# Schematic01.net
KiCad netlist of a schematic drawn in Altium Designer
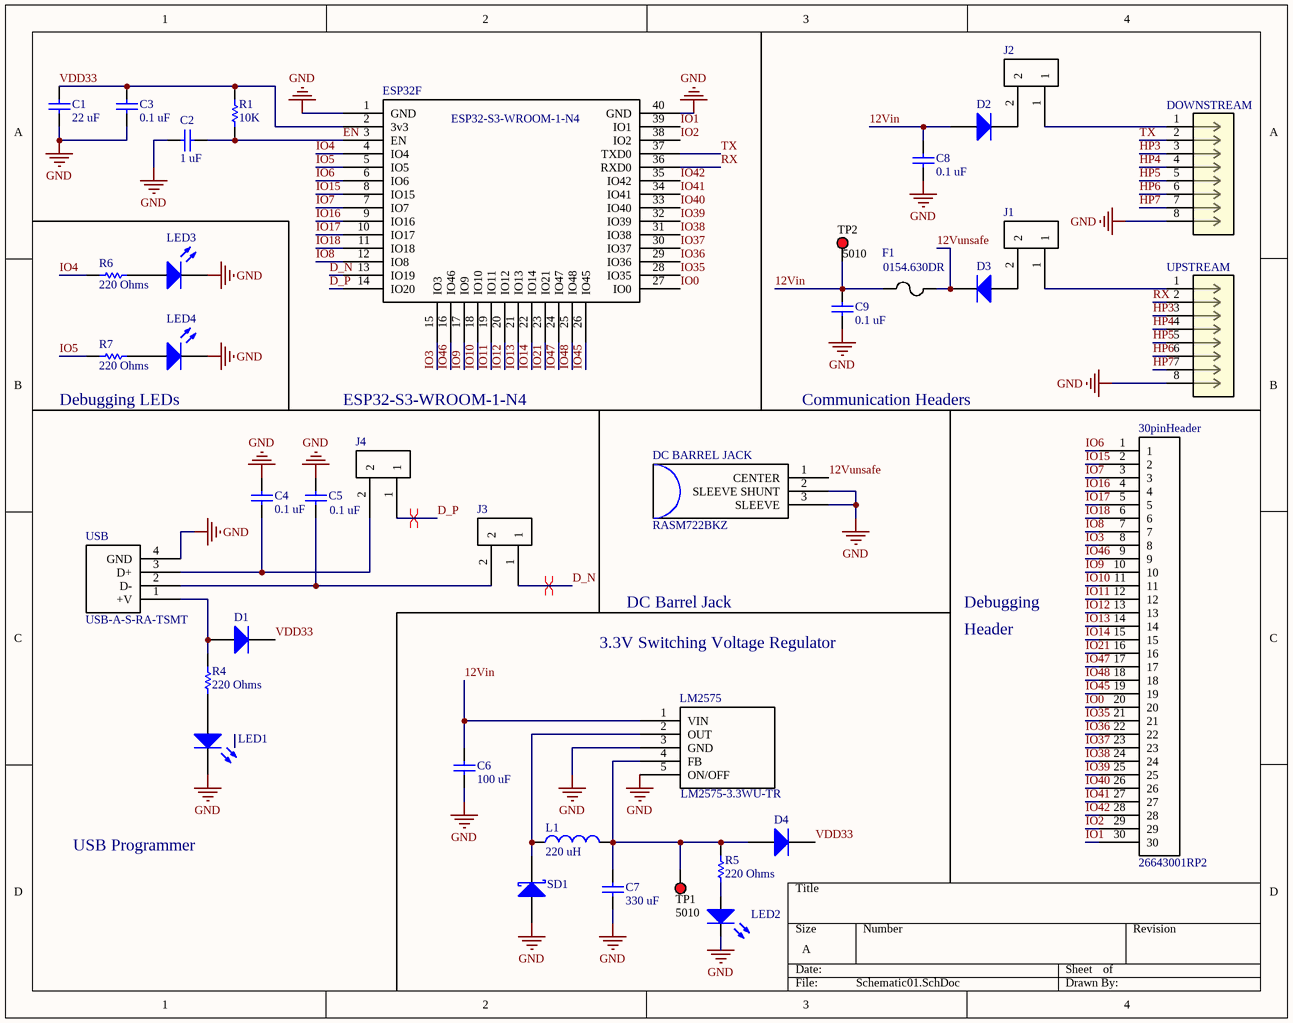
[diagram p0: Schematic01.SchDoc]

(export (version "E")
  (design (tool "Eeschema 10.0.6"))
  (components
    (comp (ref "30pinHeader")
      (value "26643001RP2")
      (description "Board Connector")
      (libsource (lib "egreetis") (part "26643001RP2-Symbol-1"))
    )
    (comp (ref "C1")
      (value "22 uF")
      (description "Capacitor")
      (libsource (lib "Simulation Generic Components") (part "Capacitor"))
    )
    (comp (ref "C2")
      (value "1 uF")
      (description "Capacitor")
      (libsource (lib "Simulation Generic Components") (part "Capacitor"))
    )
    (comp (ref "C3")
      (value "0.1 uF")
      (description "Capacitor")
      (libsource (lib "Simulation Generic Components") (part "Capacitor"))
    )
    (comp (ref "C4")
      (value "0.1 uF")
      (description "Capacitor")
      (libsource (lib "Simulation Generic Components") (part "Capacitor"))
    )
    (comp (ref "C5")
      (value "0.1 uF")
      (description "Capacitor")
      (libsource (lib "Simulation Generic Components") (part "Capacitor"))
    )
    (comp (ref "C6")
      (value "100 uF")
      (description "Capacitor")
      (libsource (lib "Simulation Generic Components") (part "Capacitor"))
    )
    (comp (ref "C7")
      (value "330 uF")
      (description "Capacitor")
      (libsource (lib "Simulation Generic Components") (part "Capacitor"))
    )
    (comp (ref "C8")
      (value "0.1 uF")
      (description "Capacitor")
      (libsource (lib "Simulation Generic Components") (part "Capacitor"))
    )
    (comp (ref "C9")
      (value "0.1 uF")
      (description "Capacitor")
      (libsource (lib "Simulation Generic Components") (part "Capacitor"))
    )
    (comp (ref "D1") (value "Diode") (libsource (lib "Simulation Generic Components") (part "Diode")))
    (comp (ref "D2") (value "Diode") (libsource (lib "Simulation Generic Components") (part "Diode")))
    (comp (ref "D3") (value "Diode") (libsource (lib "Simulation Generic Components") (part "Diode")))
    (comp (ref "D4") (value "Diode") (libsource (lib "Simulation Generic Components") (part "Diode")))
    (comp (ref "DC BARREL JACK")
      (value "RASM722BKZ")
      (description "Connector, DC Power Jack, BKZ Locking Series, 2.0mm Surface Mount")
      (libsource (lib "egreetis") (part "RASM722BKZ-Symbol-1"))
    )
    (comp (ref "DOWNSTREAM")
      (value "702460801")
      (footprint "CONN_7024608xx_MOL")
      (description "No Description Available")
      (libsource (lib "egreetis") (part "702460801"))
    )
    (comp (ref "ESP32F")
      (value "ESP32-S3-WROOM-1-N4")
      (description "WiFi-Modul 802.11/BT 2, 4-2, 5GHz 150Mb/s")
      (libsource (lib "egreetis") (part "ESP32-S3-WROOM-1-N4-Symbol-1"))
    )
    (comp (ref "F1")
      (value "0154.630DR")
      (footprint "0154Series_LTF")
      (description "No Description Available")
      (libsource (lib "0154P630DR") (part "0154.630DR"))
    )
    (comp (ref "J1")
      (value "26640201RP2")
      (description "Board Connector")
      (libsource (lib "egreetis") (part "26640201RP2-Symbol-1"))
    )
    (comp (ref "J2")
      (value "26640201RP2")
      (description "Board Connector")
      (libsource (lib "egreetis") (part "26640201RP2-Symbol-1"))
    )
    (comp (ref "J3")
      (value "26640201RP2")
      (description "Board Connector")
      (libsource (lib "egreetis") (part "26640201RP2-Symbol-1"))
    )
    (comp (ref "J4")
      (value "26640201RP2")
      (description "Board Connector")
      (libsource (lib "egreetis") (part "26640201RP2-Symbol-1"))
    )
    (comp (ref "L1")
      (value "220 uH")
      (description "Inductor")
      (libsource (lib "Simulation Generic Components") (part "Inductor"))
    )
    (comp (ref "LED1")
      (value "Light-Emitting Diode")
      (libsource (lib "Simulation Generic Components") (part "LED"))
    )
    (comp (ref "LED2")
      (value "Light-Emitting Diode")
      (libsource (lib "Simulation Generic Components") (part "LED"))
    )
    (comp (ref "LED3")
      (value "Light-Emitting Diode")
      (libsource (lib "Simulation Generic Components") (part "LED"))
    )
    (comp (ref "LED4")
      (value "Light-Emitting Diode")
      (libsource (lib "Simulation Generic Components") (part "LED"))
    )
    (comp (ref "LM2575")
      (value "LM2575-3.3WUTR")
      (description "LM2575 Series 3.3 V 1 A 52 KHz High-Efficiency Step-Down Buck Regulator-TO-263-5")
      (libsource (lib "egreetis") (part "LM2575-3.3WU-TR"))
    )
    (comp (ref "R1")
      (value "10K")
      (description "Resistor")
      (libsource (lib "Simulation Generic Components") (part "Resistor"))
    )
    (comp (ref "R4")
      (value "220 Ohms")
      (description "Resistor")
      (libsource (lib "Simulation Generic Components") (part "Resistor"))
    )
    (comp (ref "R5")
      (value "220 Ohms")
      (description "Resistor")
      (libsource (lib "Simulation Generic Components") (part "Resistor"))
    )
    (comp (ref "R6")
      (value "220 Ohms")
      (description "Resistor")
      (libsource (lib "Simulation Generic Components") (part "Resistor"))
    )
    (comp (ref "R7")
      (value "220 Ohms")
      (description "Resistor")
      (libsource (lib "Simulation Generic Components") (part "Resistor"))
    )
    (comp (ref "SD1")
      (value "Schottky Diode")
      (libsource (lib "Simulation Generic Components") (part "Schottky Diode"))
    )
    (comp (ref "TP1")
      (value "5010")
      (footprint "KSTN-5010_V")
      (description "Interconnection Device")
      (libsource (lib "egreetis") (part "TESTPOINT_RED"))
    )
    (comp (ref "TP2")
      (value "5010")
      (footprint "KSTN-5010_V")
      (description "Interconnection Device")
      (libsource (lib "egreetis") (part "TESTPOINT_RED"))
    )
    (comp (ref "UPSTREAM")
      (value "702460801")
      (footprint "CONN_7024608xx_MOL")
      (description "No Description Available")
      (libsource (lib "egreetis") (part "702460801"))
    )
    (comp (ref "USB")
      (value "USB-A-S-RA-TSMT")
      (description "Conn USB 2.0 Type A F 4 POS Solder RA SMD 4 Terminal 1 Port")
      (libsource (lib "egreetis") (part "USB-A-S-RA-TSMT-Symbol-1"))
    )
  )
  (nets
    (net (code "1") (name "/12Vin") (class "Default")
      (node (ref "C6") (pin "2") (pinfunction "2_2") (pintype "passive"))
      (node (ref "C8") (pin "2") (pinfunction "2_2") (pintype "passive"))
      (node (ref "C9") (pin "2") (pinfunction "2_2") (pintype "passive"))
      (node (ref "D2") (pin "1") (pinfunction "A_1") (pintype "passive"))
      (node (ref "F1") (pin "1") (pinfunction "1_1") (pintype "passive"))
      (node (ref "LM2575") (pin "1") (pinfunction "VIN_1") (pintype "passive"))
      (node (ref "TP2") (pin "1") (pinfunction "1_1") (pintype "passive"))
    )
    (net (code "2") (name "/12Vunsafe") (class "Default")
      (node (ref "D3") (pin "2") (pinfunction "K_2") (pintype "passive"))
      (node (ref "DC BARREL JACK") (pin "1") (pinfunction "CENTER_1") (pintype "passive"))
      (node (ref "F1") (pin "2") (pinfunction "2_2") (pintype "passive"))
    )
    (net (code "3") (name "/D_N") (class "Default")
      (node (ref "ESP32F") (pin "13") (pinfunction "IO19_13") (pintype "passive"))
      (node (ref "J3") (pin "1") (pinfunction "1_1") (pintype "passive"))
    )
    (net (code "4") (name "/D_P") (class "Default")
      (node (ref "ESP32F") (pin "14") (pinfunction "IO20_14") (pintype "passive"))
      (node (ref "J4") (pin "1") (pinfunction "1_1") (pintype "passive"))
    )
    (net (code "5") (name "/EN") (class "Default")
      (node (ref "C2") (pin "2") (pinfunction "2_2") (pintype "passive"))
      (node (ref "ESP32F") (pin "3") (pinfunction "EN_3") (pintype "passive"))
      (node (ref "R1") (pin "1") (pinfunction "1_1") (pintype "passive"))
    )
    (net (code "6") (name "/HP3") (class "Default")
      (node (ref "DOWNSTREAM") (pin "3") (pinfunction "3_3") (pintype "passive"))
      (node (ref "UPSTREAM") (pin "3") (pinfunction "3_3") (pintype "passive"))
    )
    (net (code "7") (name "/HP4") (class "Default")
      (node (ref "DOWNSTREAM") (pin "4") (pinfunction "4_4") (pintype "passive"))
      (node (ref "UPSTREAM") (pin "4") (pinfunction "4_4") (pintype "passive"))
    )
    (net (code "8") (name "/HP5") (class "Default")
      (node (ref "DOWNSTREAM") (pin "5") (pinfunction "5_5") (pintype "passive"))
      (node (ref "UPSTREAM") (pin "5") (pinfunction "5_5") (pintype "passive"))
    )
    (net (code "9") (name "/HP6") (class "Default")
      (node (ref "DOWNSTREAM") (pin "6") (pinfunction "6_6") (pintype "passive"))
      (node (ref "UPSTREAM") (pin "6") (pinfunction "6_6") (pintype "passive"))
    )
    (net (code "10") (name "/HP7") (class "Default")
      (node (ref "DOWNSTREAM") (pin "7") (pinfunction "7_7") (pintype "passive"))
      (node (ref "UPSTREAM") (pin "7") (pinfunction "7_7") (pintype "passive"))
    )
    (net (code "11") (name "/IO0") (class "Default")
      (node (ref "30pinHeader") (pin "20") (pinfunction "20_20") (pintype "passive"))
      (node (ref "ESP32F") (pin "27") (pinfunction "IO0_27") (pintype "passive"))
    )
    (net (code "12") (name "/IO1") (class "Default")
      (node (ref "30pinHeader") (pin "30") (pinfunction "30_30") (pintype "passive"))
      (node (ref "ESP32F") (pin "39") (pinfunction "IO1_39") (pintype "passive"))
    )
    (net (code "13") (name "/IO2") (class "Default")
      (node (ref "30pinHeader") (pin "29") (pinfunction "29_29") (pintype "passive"))
      (node (ref "ESP32F") (pin "38") (pinfunction "IO2_38") (pintype "passive"))
    )
    (net (code "14") (name "/IO3") (class "Default")
      (node (ref "30pinHeader") (pin "8") (pinfunction "8_8") (pintype "passive"))
      (node (ref "ESP32F") (pin "15") (pinfunction "IO3_15") (pintype "passive"))
    )
    (net (code "15") (name "/IO4") (class "Default")
      (node (ref "ESP32F") (pin "4") (pinfunction "IO4_4") (pintype "passive"))
      (node (ref "R6") (pin "1") (pinfunction "1_1") (pintype "passive"))
    )
    (net (code "16") (name "/IO5") (class "Default")
      (node (ref "ESP32F") (pin "5") (pinfunction "IO5_5") (pintype "passive"))
      (node (ref "R7") (pin "1") (pinfunction "1_1") (pintype "passive"))
    )
    (net (code "17") (name "/IO6") (class "Default")
      (node (ref "30pinHeader") (pin "1") (pinfunction "1_1") (pintype "passive"))
      (node (ref "ESP32F") (pin "6") (pinfunction "IO6_6") (pintype "passive"))
    )
    (net (code "18") (name "/IO7") (class "Default")
      (node (ref "30pinHeader") (pin "3") (pinfunction "3_3") (pintype "passive"))
      (node (ref "ESP32F") (pin "7") (pinfunction "IO7_7") (pintype "passive"))
    )
    (net (code "19") (name "/IO8") (class "Default")
      (node (ref "30pinHeader") (pin "7") (pinfunction "7_7") (pintype "passive"))
      (node (ref "ESP32F") (pin "12") (pinfunction "IO8_12") (pintype "passive"))
    )
    (net (code "20") (name "/IO9") (class "Default")
      (node (ref "30pinHeader") (pin "10") (pinfunction "10_10") (pintype "passive"))
      (node (ref "ESP32F") (pin "17") (pinfunction "IO9_17") (pintype "passive"))
    )
    (net (code "21") (name "/IO10") (class "Default")
      (node (ref "30pinHeader") (pin "11") (pinfunction "11_11") (pintype "passive"))
      (node (ref "ESP32F") (pin "18") (pinfunction "IO10_18") (pintype "passive"))
    )
    (net (code "22") (name "/IO11") (class "Default")
      (node (ref "30pinHeader") (pin "12") (pinfunction "12_12") (pintype "passive"))
      (node (ref "ESP32F") (pin "19") (pinfunction "IO11_19") (pintype "passive"))
    )
    (net (code "23") (name "/IO12") (class "Default")
      (node (ref "30pinHeader") (pin "13") (pinfunction "13_13") (pintype "passive"))
      (node (ref "ESP32F") (pin "20") (pinfunction "IO12_20") (pintype "passive"))
    )
    (net (code "24") (name "/IO13") (class "Default")
      (node (ref "30pinHeader") (pin "14") (pinfunction "14_14") (pintype "passive"))
      (node (ref "ESP32F") (pin "21") (pinfunction "IO13_21") (pintype "passive"))
    )
    (net (code "25") (name "/IO14") (class "Default")
      (node (ref "30pinHeader") (pin "15") (pinfunction "15_15") (pintype "passive"))
      (node (ref "ESP32F") (pin "22") (pinfunction "IO14_22") (pintype "passive"))
    )
    (net (code "26") (name "/IO15") (class "Default")
      (node (ref "30pinHeader") (pin "2") (pinfunction "2_2") (pintype "passive"))
      (node (ref "ESP32F") (pin "8") (pinfunction "IO15_8") (pintype "passive"))
    )
    (net (code "27") (name "/IO16") (class "Default")
      (node (ref "30pinHeader") (pin "4") (pinfunction "4_4") (pintype "passive"))
      (node (ref "ESP32F") (pin "9") (pinfunction "IO16_9") (pintype "passive"))
    )
    (net (code "28") (name "/IO17") (class "Default")
      (node (ref "30pinHeader") (pin "5") (pinfunction "5_5") (pintype "passive"))
      (node (ref "ESP32F") (pin "10") (pinfunction "IO17_10") (pintype "passive"))
    )
    (net (code "29") (name "/IO18") (class "Default")
      (node (ref "30pinHeader") (pin "6") (pinfunction "6_6") (pintype "passive"))
      (node (ref "ESP32F") (pin "11") (pinfunction "IO18_11") (pintype "passive"))
    )
    (net (code "30") (name "/IO21") (class "Default")
      (node (ref "30pinHeader") (pin "16") (pinfunction "16_16") (pintype "passive"))
      (node (ref "ESP32F") (pin "23") (pinfunction "IO21_23") (pintype "passive"))
    )
    (net (code "31") (name "/IO35") (class "Default")
      (node (ref "30pinHeader") (pin "21") (pinfunction "21_21") (pintype "passive"))
      (node (ref "ESP32F") (pin "28") (pinfunction "IO35_28") (pintype "passive"))
    )
    (net (code "32") (name "/IO36") (class "Default")
      (node (ref "30pinHeader") (pin "22") (pinfunction "22_22") (pintype "passive"))
      (node (ref "ESP32F") (pin "29") (pinfunction "IO36_29") (pintype "passive"))
    )
    (net (code "33") (name "/IO37") (class "Default")
      (node (ref "30pinHeader") (pin "23") (pinfunction "23_23") (pintype "passive"))
      (node (ref "ESP32F") (pin "30") (pinfunction "IO37_30") (pintype "passive"))
    )
    (net (code "34") (name "/IO38") (class "Default")
      (node (ref "30pinHeader") (pin "24") (pinfunction "24_24") (pintype "passive"))
      (node (ref "ESP32F") (pin "31") (pinfunction "IO38_31") (pintype "passive"))
    )
    (net (code "35") (name "/IO39") (class "Default")
      (node (ref "30pinHeader") (pin "25") (pinfunction "25_25") (pintype "passive"))
      (node (ref "ESP32F") (pin "32") (pinfunction "IO39_32") (pintype "passive"))
    )
    (net (code "36") (name "/IO40") (class "Default")
      (node (ref "30pinHeader") (pin "26") (pinfunction "26_26") (pintype "passive"))
      (node (ref "ESP32F") (pin "33") (pinfunction "IO40_33") (pintype "passive"))
    )
    (net (code "37") (name "/IO41") (class "Default")
      (node (ref "30pinHeader") (pin "27") (pinfunction "27_27") (pintype "passive"))
      (node (ref "ESP32F") (pin "34") (pinfunction "IO41_34") (pintype "passive"))
    )
    (net (code "38") (name "/IO42") (class "Default")
      (node (ref "30pinHeader") (pin "28") (pinfunction "28_28") (pintype "passive"))
      (node (ref "ESP32F") (pin "35") (pinfunction "IO42_35") (pintype "passive"))
    )
    (net (code "39") (name "/IO45") (class "Default")
      (node (ref "30pinHeader") (pin "19") (pinfunction "19_19") (pintype "passive"))
      (node (ref "ESP32F") (pin "26") (pinfunction "IO45_26") (pintype "passive"))
    )
    (net (code "40") (name "/IO46") (class "Default")
      (node (ref "30pinHeader") (pin "9") (pinfunction "9_9") (pintype "passive"))
      (node (ref "ESP32F") (pin "16") (pinfunction "IO46_16") (pintype "passive"))
    )
    (net (code "41") (name "/IO47") (class "Default")
      (node (ref "30pinHeader") (pin "17") (pinfunction "17_17") (pintype "passive"))
      (node (ref "ESP32F") (pin "24") (pinfunction "IO47_24") (pintype "passive"))
    )
    (net (code "42") (name "/IO48") (class "Default")
      (node (ref "30pinHeader") (pin "18") (pinfunction "18_18") (pintype "passive"))
      (node (ref "ESP32F") (pin "25") (pinfunction "IO48_25") (pintype "passive"))
    )
    (net (code "43") (name "/RX") (class "Default")
      (node (ref "ESP32F") (pin "36") (pinfunction "RXD0_36") (pintype "passive"))
      (node (ref "UPSTREAM") (pin "2") (pinfunction "2_2") (pintype "passive"))
    )
    (net (code "44") (name "/TX") (class "Default")
      (node (ref "DOWNSTREAM") (pin "2") (pinfunction "2_2") (pintype "passive"))
      (node (ref "ESP32F") (pin "37") (pinfunction "TXD0_37") (pintype "passive"))
    )
    (net (code "45") (name "/VDD33") (class "Default")
      (node (ref "C1") (pin "2") (pinfunction "2_2") (pintype "passive"))
      (node (ref "C3") (pin "2") (pinfunction "2_2") (pintype "passive"))
      (node (ref "D1") (pin "2") (pinfunction "K_2") (pintype "passive"))
      (node (ref "D4") (pin "2") (pinfunction "K_2") (pintype "passive"))
      (node (ref "ESP32F") (pin "2") (pinfunction "3v3_2") (pintype "passive"))
      (node (ref "R1") (pin "2") (pinfunction "2_2") (pintype "passive"))
    )
    (net (code "46") (name "GND") (class "Default")
      (node (ref "C1") (pin "1") (pinfunction "1_1") (pintype "passive"))
      (node (ref "C2") (pin "1") (pinfunction "1_1") (pintype "passive"))
      (node (ref "C3") (pin "1") (pinfunction "1_1") (pintype "passive"))
      (node (ref "C4") (pin "2") (pinfunction "2_2") (pintype "passive"))
      (node (ref "C5") (pin "2") (pinfunction "2_2") (pintype "passive"))
      (node (ref "C6") (pin "1") (pinfunction "1_1") (pintype "passive"))
      (node (ref "C7") (pin "1") (pinfunction "1_1") (pintype "passive"))
      (node (ref "C8") (pin "1") (pinfunction "1_1") (pintype "passive"))
      (node (ref "C9") (pin "1") (pinfunction "1_1") (pintype "passive"))
      (node (ref "DC BARREL JACK") (pin "2") (pinfunction "SLEEVE_SHUNT_2") (pintype "passive"))
      (node (ref "DC BARREL JACK") (pin "3") (pinfunction "SLEEVE_3") (pintype "passive"))
      (node (ref "DOWNSTREAM") (pin "8") (pinfunction "8_8") (pintype "passive"))
      (node (ref "ESP32F") (pin "1") (pinfunction "GND_1") (pintype "passive"))
      (node (ref "ESP32F") (pin "40") (pinfunction "GND_40") (pintype "passive"))
      (node (ref "LED1") (pin "2") (pinfunction "K_2") (pintype "passive"))
      (node (ref "LED2") (pin "2") (pinfunction "K_2") (pintype "passive"))
      (node (ref "LED3") (pin "2") (pinfunction "K_2") (pintype "passive"))
      (node (ref "LED4") (pin "2") (pinfunction "K_2") (pintype "passive"))
      (node (ref "LM2575") (pin "3") (pinfunction "GND_3") (pintype "passive"))
      (node (ref "LM2575") (pin "5") (pinfunction "ON/OFF_5") (pintype "passive"))
      (node (ref "SD1") (pin "1") (pinfunction "A_1") (pintype "passive"))
      (node (ref "UPSTREAM") (pin "8") (pinfunction "8_8") (pintype "passive"))
      (node (ref "USB") (pin "4") (pinfunction "GND_4") (pintype "passive"))
    )
    (net (code "47") (name "Net-(D1-A)") (class "Default")
      (node (ref "D1") (pin "1") (pinfunction "A_1") (pintype "passive"))
      (node (ref "R4") (pin "2") (pinfunction "2_2") (pintype "passive"))
      (node (ref "USB") (pin "1") (pinfunction "+V_1") (pintype "passive"))
    )
    (net (code "48") (name "Net-(D2-K)") (class "Default")
      (node (ref "D2") (pin "2") (pinfunction "K_2") (pintype "passive"))
      (node (ref "J2") (pin "2") (pinfunction "2_2") (pintype "passive"))
    )
    (net (code "49") (name "Net-(D3-A)") (class "Default")
      (node (ref "D3") (pin "1") (pinfunction "A_1") (pintype "passive"))
      (node (ref "J1") (pin "2") (pinfunction "2_2") (pintype "passive"))
    )
    (net (code "50") (name "Net-(D4-A)") (class "Default")
      (node (ref "C7") (pin "2") (pinfunction "2_2") (pintype "passive"))
      (node (ref "D4") (pin "1") (pinfunction "A_1") (pintype "passive"))
      (node (ref "L1") (pin "2") (pinfunction "2_2") (pintype "passive"))
      (node (ref "LM2575") (pin "4") (pinfunction "FB_4") (pintype "passive"))
      (node (ref "R5") (pin "2") (pinfunction "2_2") (pintype "passive"))
      (node (ref "TP1") (pin "1") (pinfunction "1_1") (pintype "passive"))
    )
    (net (code "51") (name "Net-(DOWNSTREAM-Pad1)") (class "Default")
      (node (ref "DOWNSTREAM") (pin "1") (pinfunction "1_1") (pintype "passive"))
      (node (ref "J2") (pin "1") (pinfunction "1_1") (pintype "passive"))
    )
    (net (code "52") (name "Net-(J1-Pad1)") (class "Default")
      (node (ref "J1") (pin "1") (pinfunction "1_1") (pintype "passive"))
      (node (ref "UPSTREAM") (pin "1") (pinfunction "1_1") (pintype "passive"))
    )
    (net (code "53") (name "Net-(LED1-A)") (class "Default")
      (node (ref "LED1") (pin "1") (pinfunction "A_1") (pintype "passive"))
      (node (ref "R4") (pin "1") (pinfunction "1_1") (pintype "passive"))
    )
    (net (code "54") (name "Net-(LED2-A)") (class "Default")
      (node (ref "LED2") (pin "1") (pinfunction "A_1") (pintype "passive"))
      (node (ref "R5") (pin "1") (pinfunction "1_1") (pintype "passive"))
    )
    (net (code "55") (name "Net-(LED3-A)") (class "Default")
      (node (ref "LED3") (pin "1") (pinfunction "A_1") (pintype "passive"))
      (node (ref "R6") (pin "2") (pinfunction "2_2") (pintype "passive"))
    )
    (net (code "56") (name "Net-(LED4-A)") (class "Default")
      (node (ref "LED4") (pin "1") (pinfunction "A_1") (pintype "passive"))
      (node (ref "R7") (pin "2") (pinfunction "2_2") (pintype "passive"))
    )
    (net (code "57") (name "Net-(LM2575-OUT)") (class "Default")
      (node (ref "L1") (pin "1") (pinfunction "1_1") (pintype "passive"))
      (node (ref "LM2575") (pin "2") (pinfunction "OUT_2") (pintype "passive"))
      (node (ref "SD1") (pin "2") (pinfunction "K_2") (pintype "passive"))
    )
    (net (code "58") (name "Net-(USB-D+)") (class "Default")
      (node (ref "C4") (pin "1") (pinfunction "1_1") (pintype "passive"))
      (node (ref "J4") (pin "2") (pinfunction "2_2") (pintype "passive"))
      (node (ref "USB") (pin "3") (pinfunction "D+_3") (pintype "passive"))
    )
    (net (code "59") (name "Net-(USB-D-)") (class "Default")
      (node (ref "C5") (pin "1") (pinfunction "1_1") (pintype "passive"))
      (node (ref "J3") (pin "2") (pinfunction "2_2") (pintype "passive"))
      (node (ref "USB") (pin "2") (pinfunction "D-_2") (pintype "passive"))
    )
  )
)
